# MJ818_clone_-_all_driver_-_POC.net
KiCad netlist of a schematic drawn in EAGLE
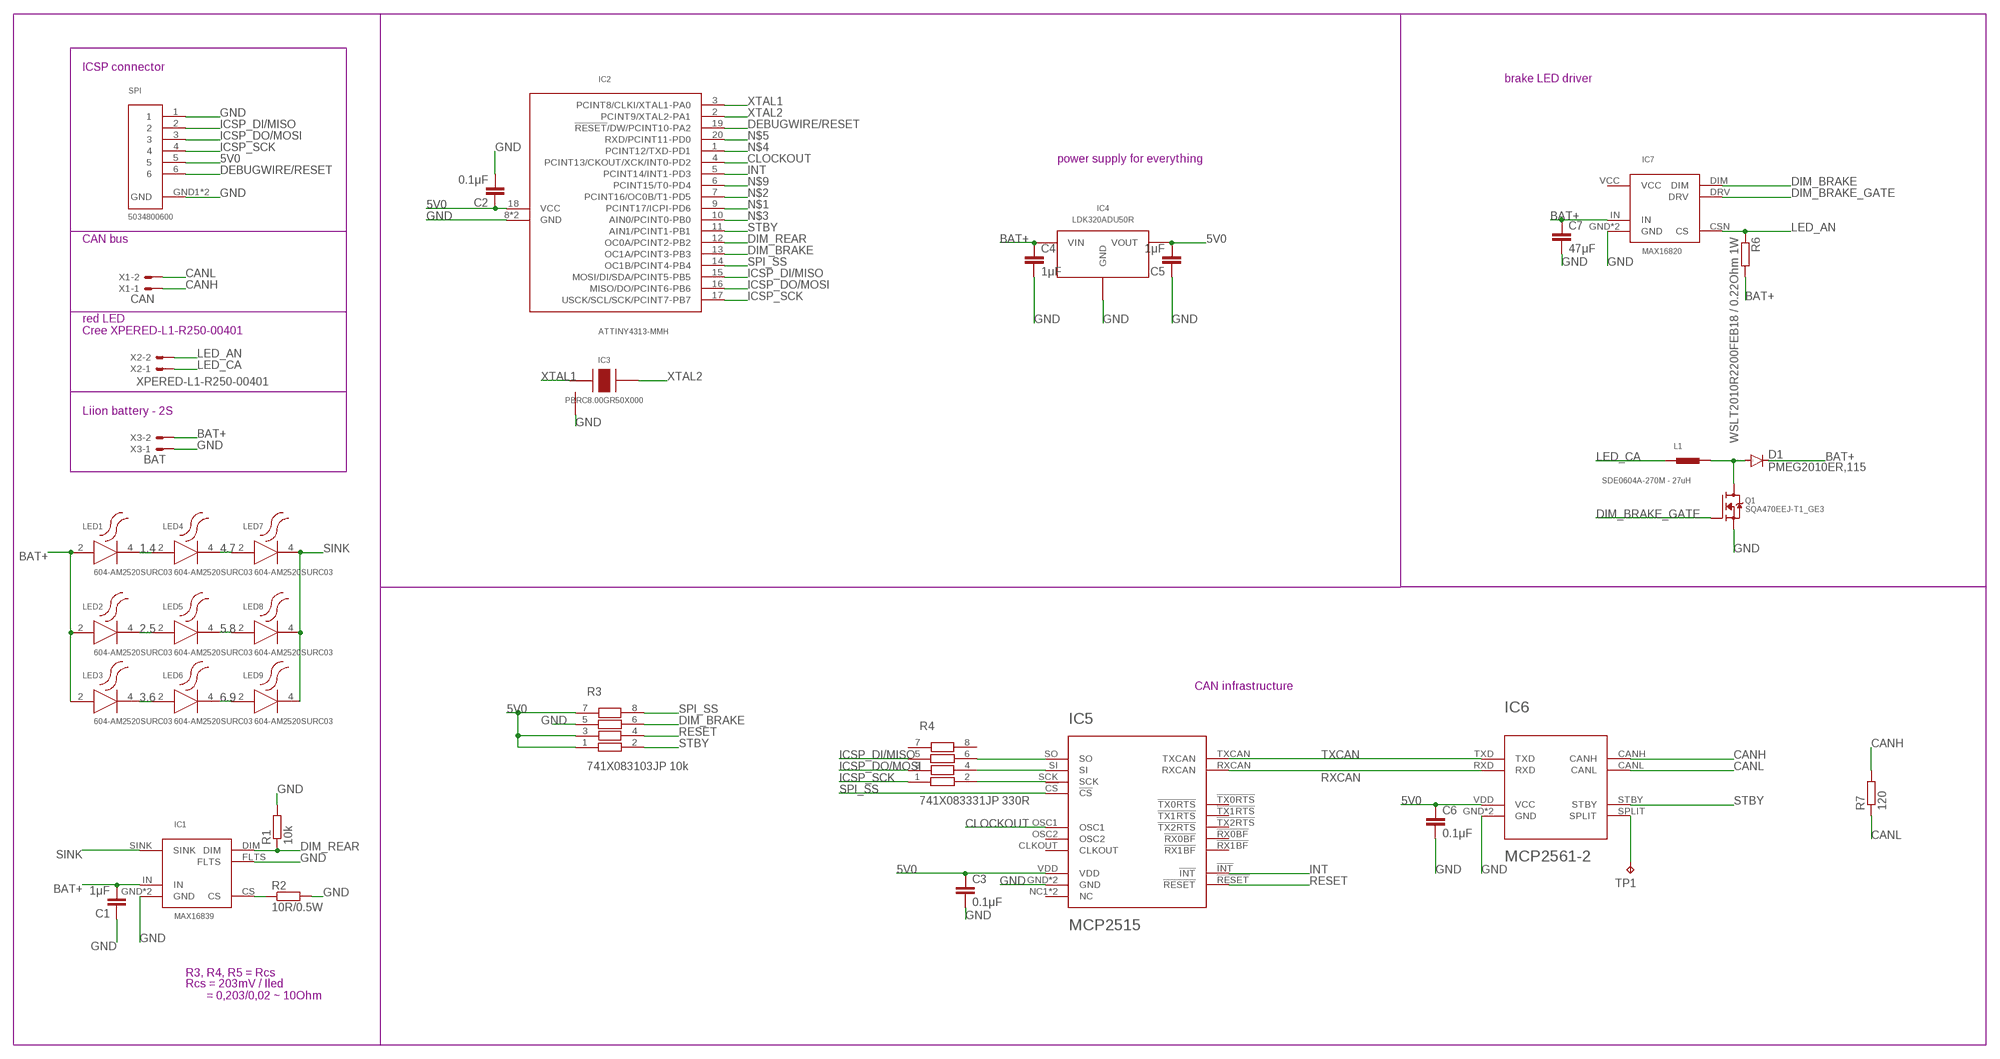
[diagram p0: schematic, sheet 1]

(export (version "E")
  (design (tool "Eeschema 10.0.6"))
  (components
    (comp (ref "C1")
      (value "1μF")
      (footprint "eagle-import:C0402")
      (libsource (lib "eagle-import") (part "C-EUC0402"))
    )
    (comp (ref "C2")
      (value "0.1μF")
      (footprint "eagle-import:C0402")
      (libsource (lib "eagle-import") (part "C-EUC0402"))
    )
    (comp (ref "C3")
      (value "0.1μF")
      (footprint "eagle-import:C0402")
      (libsource (lib "eagle-import") (part "C-EUC0402"))
    )
    (comp (ref "C4")
      (value "1μF")
      (footprint "eagle-import:C0402")
      (libsource (lib "eagle-import") (part "C-EUC0402"))
    )
    (comp (ref "C5")
      (value "1μF")
      (footprint "eagle-import:C0402")
      (libsource (lib "eagle-import") (part "C-EUC0402"))
    )
    (comp (ref "C6")
      (value "0.1μF")
      (footprint "eagle-import:C0402")
      (libsource (lib "eagle-import") (part "C-EUC0402"))
    )
    (comp (ref "C7")
      (value "47μF")
      (footprint "eagle-import:C0805")
      (libsource (lib "eagle-import") (part "C-EUC0805"))
    )
    (comp (ref "D1")
      (value "PMEG2010ER,115")
      (footprint "eagle-import:SOD123")
      (libsource (lib "eagle-import") (part "DIODE-SOD123"))
    )
    (comp (ref "IC1")
      (value "MAX16839")
      (footprint "eagle-import:TDFN-6-EP")
      (libsource (lib "eagle-import") (part "MAX16839"))
    )
    (comp (ref "IC2")
      (value "ATTINY4313-MMH")
      (footprint "eagle-import:VQFN-20")
      (fields (field (name "SPICEPREFIX") "X"))
      (libsource (lib "eagle-import") (part "ATTINY4313VQFN-20"))
    )
    (comp (ref "IC3")
      (value "PBRC8.00GR50X000")
      (footprint "eagle-import:SMT")
      (libsource (lib "eagle-import") (part "PRQV"))
    )
    (comp (ref "IC4")
      (value "LDK320ADU50R")
      (footprint "eagle-import:SOT-89-D")
      (libsource (lib "eagle-import") (part "LDO"))
    )
    (comp (ref "IC5")
      (value "MCP2515")
      (footprint "eagle-import:QFN20")
      (libsource (lib "eagle-import") (part "MCP2515-I-ML"))
    )
    (comp (ref "IC6")
      (value "MCP2561-2")
      (footprint "eagle-import:DFN10")
      (libsource (lib "eagle-import") (part "MCP2561-2"))
    )
    (comp (ref "IC7")
      (value "MAX16820")
      (footprint "eagle-import:TDFN-6-EP")
      (libsource (lib "eagle-import") (part "MAX16820"))
    )
    (comp (ref "L1")
      (value "SDE0604A-270M - 27uH")
      (footprint "eagle-import:SMT")
      (libsource (lib "eagle-import") (part "DE0604A-778075"))
    )
    (comp (ref "LED1")
      (value "604-AM2520SURC03")
      (footprint "eagle-import:SMD")
      (libsource (lib "eagle-import") (part "1374-CLM2D-RCC-ACC-1064252"))
    )
    (comp (ref "LED2")
      (value "604-AM2520SURC03")
      (footprint "eagle-import:SMD")
      (libsource (lib "eagle-import") (part "1374-CLM2D-RCC-ACC-1064252"))
    )
    (comp (ref "LED3")
      (value "604-AM2520SURC03")
      (footprint "eagle-import:SMD")
      (libsource (lib "eagle-import") (part "1374-CLM2D-RCC-ACC-1064252"))
    )
    (comp (ref "LED4")
      (value "604-AM2520SURC03")
      (footprint "eagle-import:SMD")
      (libsource (lib "eagle-import") (part "1374-CLM2D-RCC-ACC-1064252"))
    )
    (comp (ref "LED5")
      (value "604-AM2520SURC03")
      (footprint "eagle-import:SMD")
      (libsource (lib "eagle-import") (part "1374-CLM2D-RCC-ACC-1064252"))
    )
    (comp (ref "LED6")
      (value "604-AM2520SURC03")
      (footprint "eagle-import:SMD")
      (libsource (lib "eagle-import") (part "1374-CLM2D-RCC-ACC-1064252"))
    )
    (comp (ref "LED7")
      (value "604-AM2520SURC03")
      (footprint "eagle-import:SMD")
      (libsource (lib "eagle-import") (part "1374-CLM2D-RCC-ACC-1064252"))
    )
    (comp (ref "LED8")
      (value "604-AM2520SURC03")
      (footprint "eagle-import:SMD")
      (libsource (lib "eagle-import") (part "1374-CLM2D-RCC-ACC-1064252"))
    )
    (comp (ref "LED9")
      (value "604-AM2520SURC03")
      (footprint "eagle-import:SMD")
      (libsource (lib "eagle-import") (part "1374-CLM2D-RCC-ACC-1064252"))
    )
    (comp (ref "Q1")
      (value "SQA470EEJ-T1_GE3")
      (footprint "eagle-import:SC-70-6")
      (libsource (lib "eagle-import") (part "SIA456DJ"))
    )
    (comp (ref "R1")
      (value "10k")
      (footprint "eagle-import:R0402")
      (libsource (lib "eagle-import") (part "R-EU_R0402"))
    )
    (comp (ref "R2")
      (value "10R/0.5W")
      (footprint "eagle-import:R0603")
      (libsource (lib "eagle-import") (part "R-EU_R0603"))
    )
    (comp (ref "R3")
      (value "741X083103JP 10k")
      (footprint "eagle-import:0402")
      (libsource (lib "eagle-import") (part "741X083331JP"))
    )
    (comp (ref "R4")
      (value "741X083331JP 330R")
      (footprint "eagle-import:0402")
      (libsource (lib "eagle-import") (part "741X083331JP"))
    )
    (comp (ref "R6")
      (value "WSLT2010R2200FEB18 / 0.22Ohm 1W")
      (footprint "eagle-import:R2010")
      (libsource (lib "eagle-import") (part "R-EU_R2010"))
    )
    (comp (ref "R7")
      (value "120")
      (footprint "eagle-import:R0805")
      (libsource (lib "eagle-import") (part "R-EU_R0805"))
    )
    (comp (ref "SPI")
      (value "5034800600")
      (footprint "eagle-import:SMT")
      (libsource (lib "eagle-import") (part "5034800600"))
    )
    (comp (ref "TP1")
      (value "TPB2,54")
      (footprint "eagle-import:B2,54")
      (libsource (lib "eagle-import") (part "TPB2,54"))
    )
    (comp (ref "X1")
      (value "CAN")
      (footprint "eagle-import:22-23-2021")
      (fields (field (name "MF") "MOLEX") (field (name "MPN") "22-23-2021"))
      (libsource (lib "eagle-import") (part "22-23-2021"))
    )
    (comp (ref "X2")
      (value "XPERED-L1-R250-00401")
      (footprint "eagle-import:22-23-2021")
      (fields (field (name "MF") "MOLEX") (field (name "MPN") "22-23-2021"))
      (libsource (lib "eagle-import") (part "22-23-2021"))
    )
    (comp (ref "X3")
      (value "BAT")
      (footprint "eagle-import:22-23-2021")
      (fields (field (name "MF") "MOLEX") (field (name "MPN") "22-23-2021"))
      (libsource (lib "eagle-import") (part "22-23-2021"))
    )
  )
  (nets
    (net (code "1") (name "/1.4") (class "Default")
      (node (ref "LED1") (pin "4") (pinfunction "C_4") (pintype "bidirectional"))
      (node (ref "LED4") (pin "2") (pinfunction "A_2") (pintype "bidirectional"))
    )
    (net (code "2") (name "/2.5") (class "Default")
      (node (ref "LED2") (pin "4") (pinfunction "C_4") (pintype "bidirectional"))
      (node (ref "LED5") (pin "2") (pinfunction "A_2") (pintype "bidirectional"))
    )
    (net (code "3") (name "/3.6") (class "Default")
      (node (ref "LED3") (pin "4") (pinfunction "C_4") (pintype "bidirectional"))
      (node (ref "LED6") (pin "2") (pinfunction "A_2") (pintype "bidirectional"))
    )
    (net (code "4") (name "/4.7") (class "Default")
      (node (ref "LED4") (pin "4") (pinfunction "C_4") (pintype "bidirectional"))
      (node (ref "LED7") (pin "2") (pinfunction "A_2") (pintype "bidirectional"))
    )
    (net (code "5") (name "/5.8") (class "Default")
      (node (ref "LED5") (pin "4") (pinfunction "C_4") (pintype "bidirectional"))
      (node (ref "LED8") (pin "2") (pinfunction "A_2") (pintype "bidirectional"))
    )
    (net (code "6") (name "/5V0") (class "Default")
      (node (ref "C2") (pin "1") (pinfunction "1_1") (pintype "passive"))
      (node (ref "C3") (pin "1") (pinfunction "1_1") (pintype "passive"))
      (node (ref "C5") (pin "2") (pinfunction "2_2") (pintype "passive"))
      (node (ref "C6") (pin "1") (pinfunction "1_1") (pintype "passive"))
      (node (ref "IC2") (pin "18") (pinfunction "VCC_18") (pintype "bidirectional"))
      (node (ref "IC4") (pin "VOUT") (pinfunction "VOUT_VOUT") (pintype "bidirectional"))
      (node (ref "IC5") (pin "VDD") (pinfunction "VDD_VDD") (pintype "power_in"))
      (node (ref "IC6") (pin "VDD") (pinfunction "VCC_VDD") (pintype "power_in"))
      (node (ref "R3") (pin "1") (pinfunction "1_1") (pintype "bidirectional"))
      (node (ref "R3") (pin "3") (pinfunction "3_3") (pintype "bidirectional"))
      (node (ref "R3") (pin "7") (pinfunction "7_7") (pintype "bidirectional"))
      (node (ref "SPI") (pin "5") (pinfunction "5_5") (pintype "bidirectional"))
    )
    (net (code "7") (name "/6.9") (class "Default")
      (node (ref "LED6") (pin "4") (pinfunction "C_4") (pintype "bidirectional"))
      (node (ref "LED9") (pin "2") (pinfunction "A_2") (pintype "bidirectional"))
    )
    (net (code "8") (name "/BAT+") (class "Default")
      (node (ref "C1") (pin "2") (pinfunction "2_2") (pintype "passive"))
      (node (ref "C4") (pin "1") (pinfunction "1_1") (pintype "passive"))
      (node (ref "C7") (pin "1") (pinfunction "1_1") (pintype "passive"))
      (node (ref "D1") (pin "C") (pinfunction "C_C") (pintype "passive"))
      (node (ref "IC1") (pin "IN") (pinfunction "IN_IN") (pintype "power_in"))
      (node (ref "IC4") (pin "VIN") (pinfunction "VIN_VIN") (pintype "bidirectional"))
      (node (ref "IC7") (pin "IN") (pinfunction "IN_IN") (pintype "power_in"))
      (node (ref "LED1") (pin "2") (pinfunction "A_2") (pintype "bidirectional"))
      (node (ref "LED2") (pin "2") (pinfunction "A_2") (pintype "bidirectional"))
      (node (ref "LED3") (pin "2") (pinfunction "A_2") (pintype "bidirectional"))
      (node (ref "R6") (pin "2") (pinfunction "2_2") (pintype "passive"))
      (node (ref "X3") (pin "2") (pinfunction "S_2") (pintype "passive"))
    )
    (net (code "9") (name "/CANH") (class "Default")
      (node (ref "IC6") (pin "CANH") (pinfunction "CANH_CANH") (pintype "bidirectional"))
      (node (ref "R7") (pin "2") (pinfunction "2_2") (pintype "passive"))
      (node (ref "X1") (pin "1") (pinfunction "S_1") (pintype "passive"))
    )
    (net (code "10") (name "/CANL") (class "Default")
      (node (ref "IC6") (pin "CANL") (pinfunction "CANL_CANL") (pintype "bidirectional"))
      (node (ref "R7") (pin "1") (pinfunction "1_1") (pintype "passive"))
      (node (ref "X1") (pin "2") (pinfunction "S_2") (pintype "passive"))
    )
    (net (code "11") (name "/CLOCKOUT") (class "Default")
      (node (ref "IC2") (pin "4") (pinfunction "PCINT13/CKOUT/XCK/INT0-PD2_4") (pintype "bidirectional"))
      (node (ref "IC5") (pin "OSC1") (pinfunction "OSC1_OSC1") (pintype "bidirectional"))
    )
    (net (code "12") (name "/DEBUGWIRE{slash}RESET") (class "Default")
      (node (ref "IC2") (pin "19") (pinfunction "~{RESET}/DW/PCINT10-PA2_19") (pintype "bidirectional"))
      (node (ref "SPI") (pin "6") (pinfunction "6_6") (pintype "bidirectional"))
    )
    (net (code "13") (name "/DIM_BRAKE") (class "Default")
      (node (ref "IC2") (pin "13") (pinfunction "OC1A/PCINT3-PB3_13") (pintype "bidirectional"))
      (node (ref "IC7") (pin "DIM") (pinfunction "DIM_DIM") (pintype "bidirectional"))
      (node (ref "R3") (pin "6") (pinfunction "6_6") (pintype "bidirectional"))
    )
    (net (code "14") (name "/DIM_BRAKE_GATE") (class "Default")
      (node (ref "IC7") (pin "DRV") (pinfunction "DRV_DRV") (pintype "bidirectional"))
      (node (ref "Q1") (pin "G") (pinfunction "G_G") (pintype "passive"))
    )
    (net (code "15") (name "/DIM_REAR") (class "Default")
      (node (ref "IC1") (pin "DIM") (pinfunction "DIM_DIM") (pintype "bidirectional"))
      (node (ref "IC2") (pin "12") (pinfunction "OC0A/PCINT2-PB2_12") (pintype "bidirectional"))
      (node (ref "R1") (pin "1") (pinfunction "1_1") (pintype "passive"))
    )
    (net (code "16") (name "/GND") (class "Default")
      (node (ref "C1") (pin "1") (pinfunction "1_1") (pintype "passive"))
      (node (ref "C2") (pin "2") (pinfunction "2_2") (pintype "passive"))
      (node (ref "C3") (pin "2") (pinfunction "2_2") (pintype "passive"))
      (node (ref "C4") (pin "2") (pinfunction "2_2") (pintype "passive"))
      (node (ref "C5") (pin "1") (pinfunction "1_1") (pintype "passive"))
      (node (ref "C6") (pin "2") (pinfunction "2_2") (pintype "passive"))
      (node (ref "C7") (pin "2") (pinfunction "2_2") (pintype "passive"))
      (node (ref "IC1") (pin "FLTS") (pinfunction "FLTS_FLTS") (pintype "bidirectional"))
      (node (ref "IC1") (pin "GND") (pinfunction "GND_GND") (pintype "power_in"))
      (node (ref "IC1") (pin "GND1") (pinfunction "GND_GND1") (pintype "power_in"))
      (node (ref "IC2") (pin "8") (pinfunction "GND_8") (pintype "bidirectional"))
      (node (ref "IC2") (pin "GND") (pinfunction "GND_GND") (pintype "bidirectional"))
      (node (ref "IC3") (pin "GND") (pinfunction "GND_GND") (pintype "bidirectional"))
      (node (ref "IC4") (pin "GND") (pinfunction "GND_GND") (pintype "bidirectional"))
      (node (ref "IC5") (pin "GND") (pinfunction "GND_GND") (pintype "power_in"))
      (node (ref "IC5") (pin "GND6") (pinfunction "GND_GND6") (pintype "power_in"))
      (node (ref "IC6") (pin "GND") (pinfunction "GND_GND") (pintype "power_in"))
      (node (ref "IC6") (pin "VSS") (pinfunction "GND_VSS") (pintype "power_in"))
      (node (ref "IC7") (pin "GND") (pinfunction "GND_GND") (pintype "power_in"))
      (node (ref "IC7") (pin "GND1") (pinfunction "GND_GND1") (pintype "power_in"))
      (node (ref "Q1") (pin "S") (pinfunction "S_S") (pintype "passive"))
      (node (ref "R1") (pin "2") (pinfunction "2_2") (pintype "passive"))
      (node (ref "R2") (pin "2") (pinfunction "2_2") (pintype "passive"))
      (node (ref "R3") (pin "5") (pinfunction "5_5") (pintype "bidirectional"))
      (node (ref "SPI") (pin "1") (pinfunction "1_1") (pintype "bidirectional"))
      (node (ref "SPI") (pin "GND1") (pinfunction "GND_GND1") (pintype "bidirectional"))
      (node (ref "SPI") (pin "GND2") (pinfunction "GND_GND2") (pintype "bidirectional"))
      (node (ref "X3") (pin "1") (pinfunction "S_1") (pintype "passive"))
    )
    (net (code "17") (name "/ICSP_DI{slash}MISO") (class "Default")
      (node (ref "IC2") (pin "15") (pinfunction "MOSI/DI/SDA/PCINT5-PB5_15") (pintype "bidirectional"))
      (node (ref "R4") (pin "5") (pinfunction "5_5") (pintype "bidirectional"))
      (node (ref "SPI") (pin "2") (pinfunction "2_2") (pintype "bidirectional"))
    )
    (net (code "18") (name "/ICSP_DO{slash}MOSI") (class "Default")
      (node (ref "IC2") (pin "16") (pinfunction "MISO/DO/PCINT6-PB6_16") (pintype "bidirectional"))
      (node (ref "R4") (pin "3") (pinfunction "3_3") (pintype "bidirectional"))
      (node (ref "SPI") (pin "3") (pinfunction "3_3") (pintype "bidirectional"))
    )
    (net (code "19") (name "/ICSP_SCK") (class "Default")
      (node (ref "IC2") (pin "17") (pinfunction "USCK/SCL/SCK/PCINT7-PB7_17") (pintype "bidirectional"))
      (node (ref "R4") (pin "1") (pinfunction "1_1") (pintype "bidirectional"))
      (node (ref "SPI") (pin "4") (pinfunction "4_4") (pintype "bidirectional"))
    )
    (net (code "20") (name "/INT") (class "Default")
      (node (ref "IC2") (pin "5") (pinfunction "PCINT14/INT1-PD3_5") (pintype "bidirectional"))
      (node (ref "IC5") (pin "!INT!") (pinfunction "~{INT}_!INT!") (pintype "bidirectional"))
    )
    (net (code "21") (name "/LED_AN") (class "Default")
      (node (ref "IC7") (pin "CSN") (pinfunction "CS_CSN") (pintype "bidirectional"))
      (node (ref "R6") (pin "1") (pinfunction "1_1") (pintype "passive"))
      (node (ref "X2") (pin "2") (pinfunction "S_2") (pintype "passive"))
    )
    (net (code "22") (name "/LED_CA") (class "Default")
      (node (ref "L1") (pin "P$1") (pinfunction "P$1_P$1") (pintype "bidirectional"))
      (node (ref "X2") (pin "1") (pinfunction "S_1") (pintype "passive"))
    )
    (net (code "23") (name "/N$1") (class "Default")
      (node (ref "IC2") (pin "9") (pinfunction "PCINT17/ICPI-PD6_9") (pintype "bidirectional"))
    )
    (net (code "24") (name "/N$2") (class "Default")
      (node (ref "IC2") (pin "7") (pinfunction "PCINT16/OC0B/T1-PD5_7") (pintype "bidirectional"))
    )
    (net (code "25") (name "/N$3") (class "Default")
      (node (ref "IC2") (pin "10") (pinfunction "AIN0/PCINT0-PB0_10") (pintype "bidirectional"))
    )
    (net (code "26") (name "/N$4") (class "Default")
      (node (ref "IC2") (pin "1") (pinfunction "PCINT12/TXD-PD1_1") (pintype "bidirectional"))
    )
    (net (code "27") (name "/N$5") (class "Default")
      (node (ref "IC2") (pin "20") (pinfunction "RXD/PCINT11-PD0_20") (pintype "bidirectional"))
    )
    (net (code "28") (name "/N$9") (class "Default")
      (node (ref "IC2") (pin "6") (pinfunction "PCINT15/T0-PD4_6") (pintype "bidirectional"))
    )
    (net (code "29") (name "/RESET") (class "Default")
      (node (ref "IC5") (pin "!RESET!") (pinfunction "~{RESET}_!RESET!") (pintype "bidirectional"))
      (node (ref "R3") (pin "4") (pinfunction "4_4") (pintype "bidirectional"))
    )
    (net (code "30") (name "/RXCAN") (class "Default")
      (node (ref "IC5") (pin "RXCAN") (pinfunction "RXCAN_RXCAN") (pintype "input"))
      (node (ref "IC6") (pin "RXD") (pinfunction "RXD_RXD") (pintype "output"))
    )
    (net (code "31") (name "/SINK") (class "Default")
      (node (ref "IC1") (pin "SINK") (pinfunction "SINK_SINK") (pintype "power_in"))
      (node (ref "LED7") (pin "4") (pinfunction "C_4") (pintype "bidirectional"))
      (node (ref "LED8") (pin "4") (pinfunction "C_4") (pintype "bidirectional"))
      (node (ref "LED9") (pin "4") (pinfunction "C_4") (pintype "bidirectional"))
    )
    (net (code "32") (name "/SPI_SS") (class "Default")
      (node (ref "IC2") (pin "14") (pinfunction "OC1B/PCINT4-PB4_14") (pintype "bidirectional"))
      (node (ref "IC5") (pin "!CS!") (pinfunction "~{CS}_!CS!") (pintype "bidirectional"))
      (node (ref "R3") (pin "8") (pinfunction "8_8") (pintype "bidirectional"))
    )
    (net (code "33") (name "/STBY") (class "Default")
      (node (ref "IC2") (pin "11") (pinfunction "AIN1/PCINT1-PB1_11") (pintype "bidirectional"))
      (node (ref "IC6") (pin "STBY") (pinfunction "STBY_STBY") (pintype "bidirectional"))
      (node (ref "R3") (pin "2") (pinfunction "2_2") (pintype "bidirectional"))
    )
    (net (code "34") (name "/TXCAN") (class "Default")
      (node (ref "IC5") (pin "TXCAN") (pinfunction "TXCAN_TXCAN") (pintype "output"))
      (node (ref "IC6") (pin "TXD") (pinfunction "TXD_TXD") (pintype "input"))
    )
    (net (code "35") (name "/VCC") (class "Default")
      (node (ref "IC7") (pin "VCC") (pinfunction "VCC_VCC") (pintype "power_in"))
    )
    (net (code "36") (name "/XTAL1") (class "Default")
      (node (ref "IC2") (pin "3") (pinfunction "PCINT8/CLKI/XTAL1-PA0_3") (pintype "bidirectional"))
      (node (ref "IC3") (pin "XTAL1") (pinfunction "XTAL1_XTAL1") (pintype "bidirectional"))
    )
    (net (code "37") (name "/XTAL2") (class "Default")
      (node (ref "IC2") (pin "2") (pinfunction "PCINT9/XTAL2-PA1_2") (pintype "bidirectional"))
      (node (ref "IC3") (pin "XTAL2") (pinfunction "XTAL2_XTAL2") (pintype "bidirectional"))
    )
    (net (code "38") (name "Net-(D1-PadA)") (class "Default")
      (node (ref "D1") (pin "A") (pinfunction "A_A") (pintype "passive"))
      (node (ref "L1") (pin "P$2") (pinfunction "P$2_P$2") (pintype "bidirectional"))
      (node (ref "Q1") (pin "D") (pinfunction "D_D") (pintype "passive"))
    )
    (net (code "39") (name "Net-(IC1-PadCS)") (class "Default")
      (node (ref "IC1") (pin "CS") (pinfunction "CS_CS") (pintype "bidirectional"))
      (node (ref "R2") (pin "1") (pinfunction "1_1") (pintype "passive"))
    )
    (net (code "40") (name "Net-(IC5-PadSCK)") (class "Default")
      (node (ref "IC5") (pin "SCK") (pinfunction "SCK_SCK") (pintype "bidirectional"))
      (node (ref "R4") (pin "2") (pinfunction "2_2") (pintype "bidirectional"))
    )
    (net (code "41") (name "Net-(IC5-PadSI)") (class "Default")
      (node (ref "IC5") (pin "SI") (pinfunction "SI_SI") (pintype "input"))
      (node (ref "R4") (pin "4") (pinfunction "4_4") (pintype "bidirectional"))
    )
    (net (code "42") (name "Net-(IC5-PadSO)") (class "Default")
      (node (ref "IC5") (pin "SO") (pinfunction "SO_SO") (pintype "output"))
      (node (ref "R4") (pin "6") (pinfunction "6_6") (pintype "bidirectional"))
    )
    (net (code "43") (name "Net-(IC6-PadSPLIT)") (class "Default")
      (node (ref "IC6") (pin "SPLIT") (pinfunction "SPLIT_SPLIT") (pintype "bidirectional"))
      (node (ref "TP1") (pin "TP") (pinfunction "TP_TP") (pintype "input"))
    )
    (net (code "44") (name "unconnected-(IC5-NC-PadNC1)") (class "Default")
      (node (ref "IC5") (pin "NC1") (pinfunction "NC_NC1") (pintype "no_connect"))
    )
    (net (code "45") (name "unconnected-(IC5-NC-PadNC2)") (class "Default")
      (node (ref "IC5") (pin "NC2") (pinfunction "NC_NC2") (pintype "no_connect"))
    )
    (net (code "46") (name "unconnected-(IC5-PadCLKOUT)") (class "Default")
      (node (ref "IC5") (pin "CLKOUT") (pinfunction "CLKOUT_CLKOUT") (pintype "bidirectional"))
    )
    (net (code "47") (name "unconnected-(IC5-PadOSC2)") (class "Default")
      (node (ref "IC5") (pin "OSC2") (pinfunction "OSC2_OSC2") (pintype "bidirectional"))
    )
    (net (code "48") (name "unconnected-(IC5-~{RX0BF}-Pad!RX0BF!)") (class "Default")
      (node (ref "IC5") (pin "!RX0BF!") (pinfunction "~{RX0BF}_!RX0BF!") (pintype "bidirectional"))
    )
    (net (code "49") (name "unconnected-(IC5-~{RX1BF}-Pad!RX1BF!)") (class "Default")
      (node (ref "IC5") (pin "!RX1BF!") (pinfunction "~{RX1BF}_!RX1BF!") (pintype "bidirectional"))
    )
    (net (code "50") (name "unconnected-(IC5-~{TX0RTS}-Pad!TX0RTS!)") (class "Default")
      (node (ref "IC5") (pin "!TX0RTS!") (pinfunction "~{TX0RTS}_!TX0RTS!") (pintype "bidirectional"))
    )
    (net (code "51") (name "unconnected-(IC5-~{TX1RTS}-Pad!TX1RTS!)") (class "Default")
      (node (ref "IC5") (pin "!TX1RTS!") (pinfunction "~{TX1RTS}_!TX1RTS!") (pintype "bidirectional"))
    )
    (net (code "52") (name "unconnected-(IC5-~{TX2RTS}-Pad!TX2RTS!)") (class "Default")
      (node (ref "IC5") (pin "!TX2RTS!") (pinfunction "~{TX2RTS}_!TX2RTS!") (pintype "bidirectional"))
    )
    (net (code "53") (name "unconnected-(R4-Pad7)") (class "Default")
      (node (ref "R4") (pin "7") (pinfunction "7_7") (pintype "bidirectional"))
    )
    (net (code "54") (name "unconnected-(R4-Pad8)") (class "Default")
      (node (ref "R4") (pin "8") (pinfunction "8_8") (pintype "bidirectional"))
    )
  )
)
